# RS485.net
KiCad netlist of a schematic drawn in Altium Designer
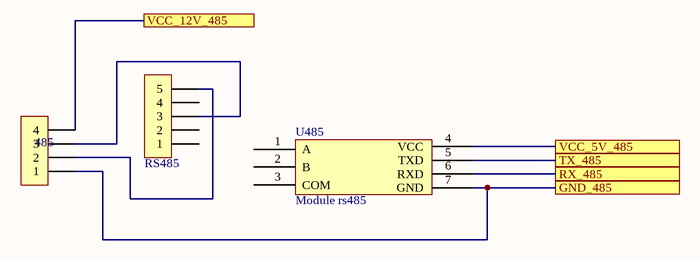
[diagram p0: RS485.SchDoc]

(export (version "E")
  (design (tool "Eeschema 10.0.6"))
  (components
    (comp (ref "485")
      (value "Header 4P 2.54 Duc Thang")
      (footprint "XH2.54M-4")
      (description "Cắm")
      (libsource (lib "Altium_Lib_by_KhueNguyenCreator") (part "Header 4P 2.54 Duc Thang"))
    )
    (comp (ref "RS485")
      (value "Header 5P 2.54 Duc Thang")
      (footprint "XH2.54M-5")
      (description "Cắm")
      (libsource (lib "Altium_Lib_by_KhueNguyenCreator") (part "Header 5P 2.54 Duc Thang"))
    )
    (comp (ref "U485")
      (value "Module rs485")
      (footprint "RS485")
      (libsource (lib "BKRES_Schlib") (part "Module rs485"))
    )
  )
  (nets
    (net (code "1") (name "/GND_485") (class "Default")
      (node (ref "485") (pin "1") (pinfunction "1_1") (pintype "passive"))
      (node (ref "U485") (pin "7") (pinfunction "GND_7") (pintype "passive"))
    )
    (net (code "2") (name "/RX_485") (class "Default")
      (node (ref "U485") (pin "6") (pinfunction "RXD_6") (pintype "passive"))
    )
    (net (code "3") (name "/TX_485") (class "Default")
      (node (ref "U485") (pin "5") (pinfunction "TXD_5") (pintype "passive"))
    )
    (net (code "4") (name "/VCC_5V_485") (class "Default")
      (node (ref "U485") (pin "4") (pinfunction "VCC_4") (pintype "passive"))
    )
    (net (code "5") (name "/VCC_12V_485") (class "Default")
      (node (ref "485") (pin "4") (pinfunction "4_4") (pintype "passive"))
    )
    (net (code "6") (name "Net-(485-Pad2)") (class "Default")
      (node (ref "485") (pin "2") (pinfunction "2_2") (pintype "passive"))
      (node (ref "RS485") (pin "5") (pinfunction "5_5") (pintype "passive"))
    )
    (net (code "7") (name "Net-(485-Pad3)") (class "Default")
      (node (ref "485") (pin "3") (pinfunction "3_3") (pintype "passive"))
      (node (ref "RS485") (pin "3") (pinfunction "3_3") (pintype "passive"))
    )
    (net (code "8") (name "unconnected-(RS485-Pad1)") (class "Default")
      (node (ref "RS485") (pin "1") (pinfunction "1_1") (pintype "passive"))
    )
    (net (code "9") (name "unconnected-(RS485-Pad2)") (class "Default")
      (node (ref "RS485") (pin "2") (pinfunction "2_2") (pintype "passive"))
    )
    (net (code "10") (name "unconnected-(RS485-Pad4)") (class "Default")
      (node (ref "RS485") (pin "4") (pinfunction "4_4") (pintype "passive"))
    )
    (net (code "11") (name "unconnected-(U485-A-Pad1)") (class "Default")
      (node (ref "U485") (pin "1") (pinfunction "A_1") (pintype "passive"))
    )
    (net (code "12") (name "unconnected-(U485-B-Pad2)") (class "Default")
      (node (ref "U485") (pin "2") (pinfunction "B_2") (pintype "passive"))
    )
    (net (code "13") (name "unconnected-(U485-COM-Pad3)") (class "Default")
      (node (ref "U485") (pin "3") (pinfunction "COM_3") (pintype "passive"))
    )
  )
)
